# CH32V467VET-R0.net
KiCad netlist of a schematic drawn in Altium Designer
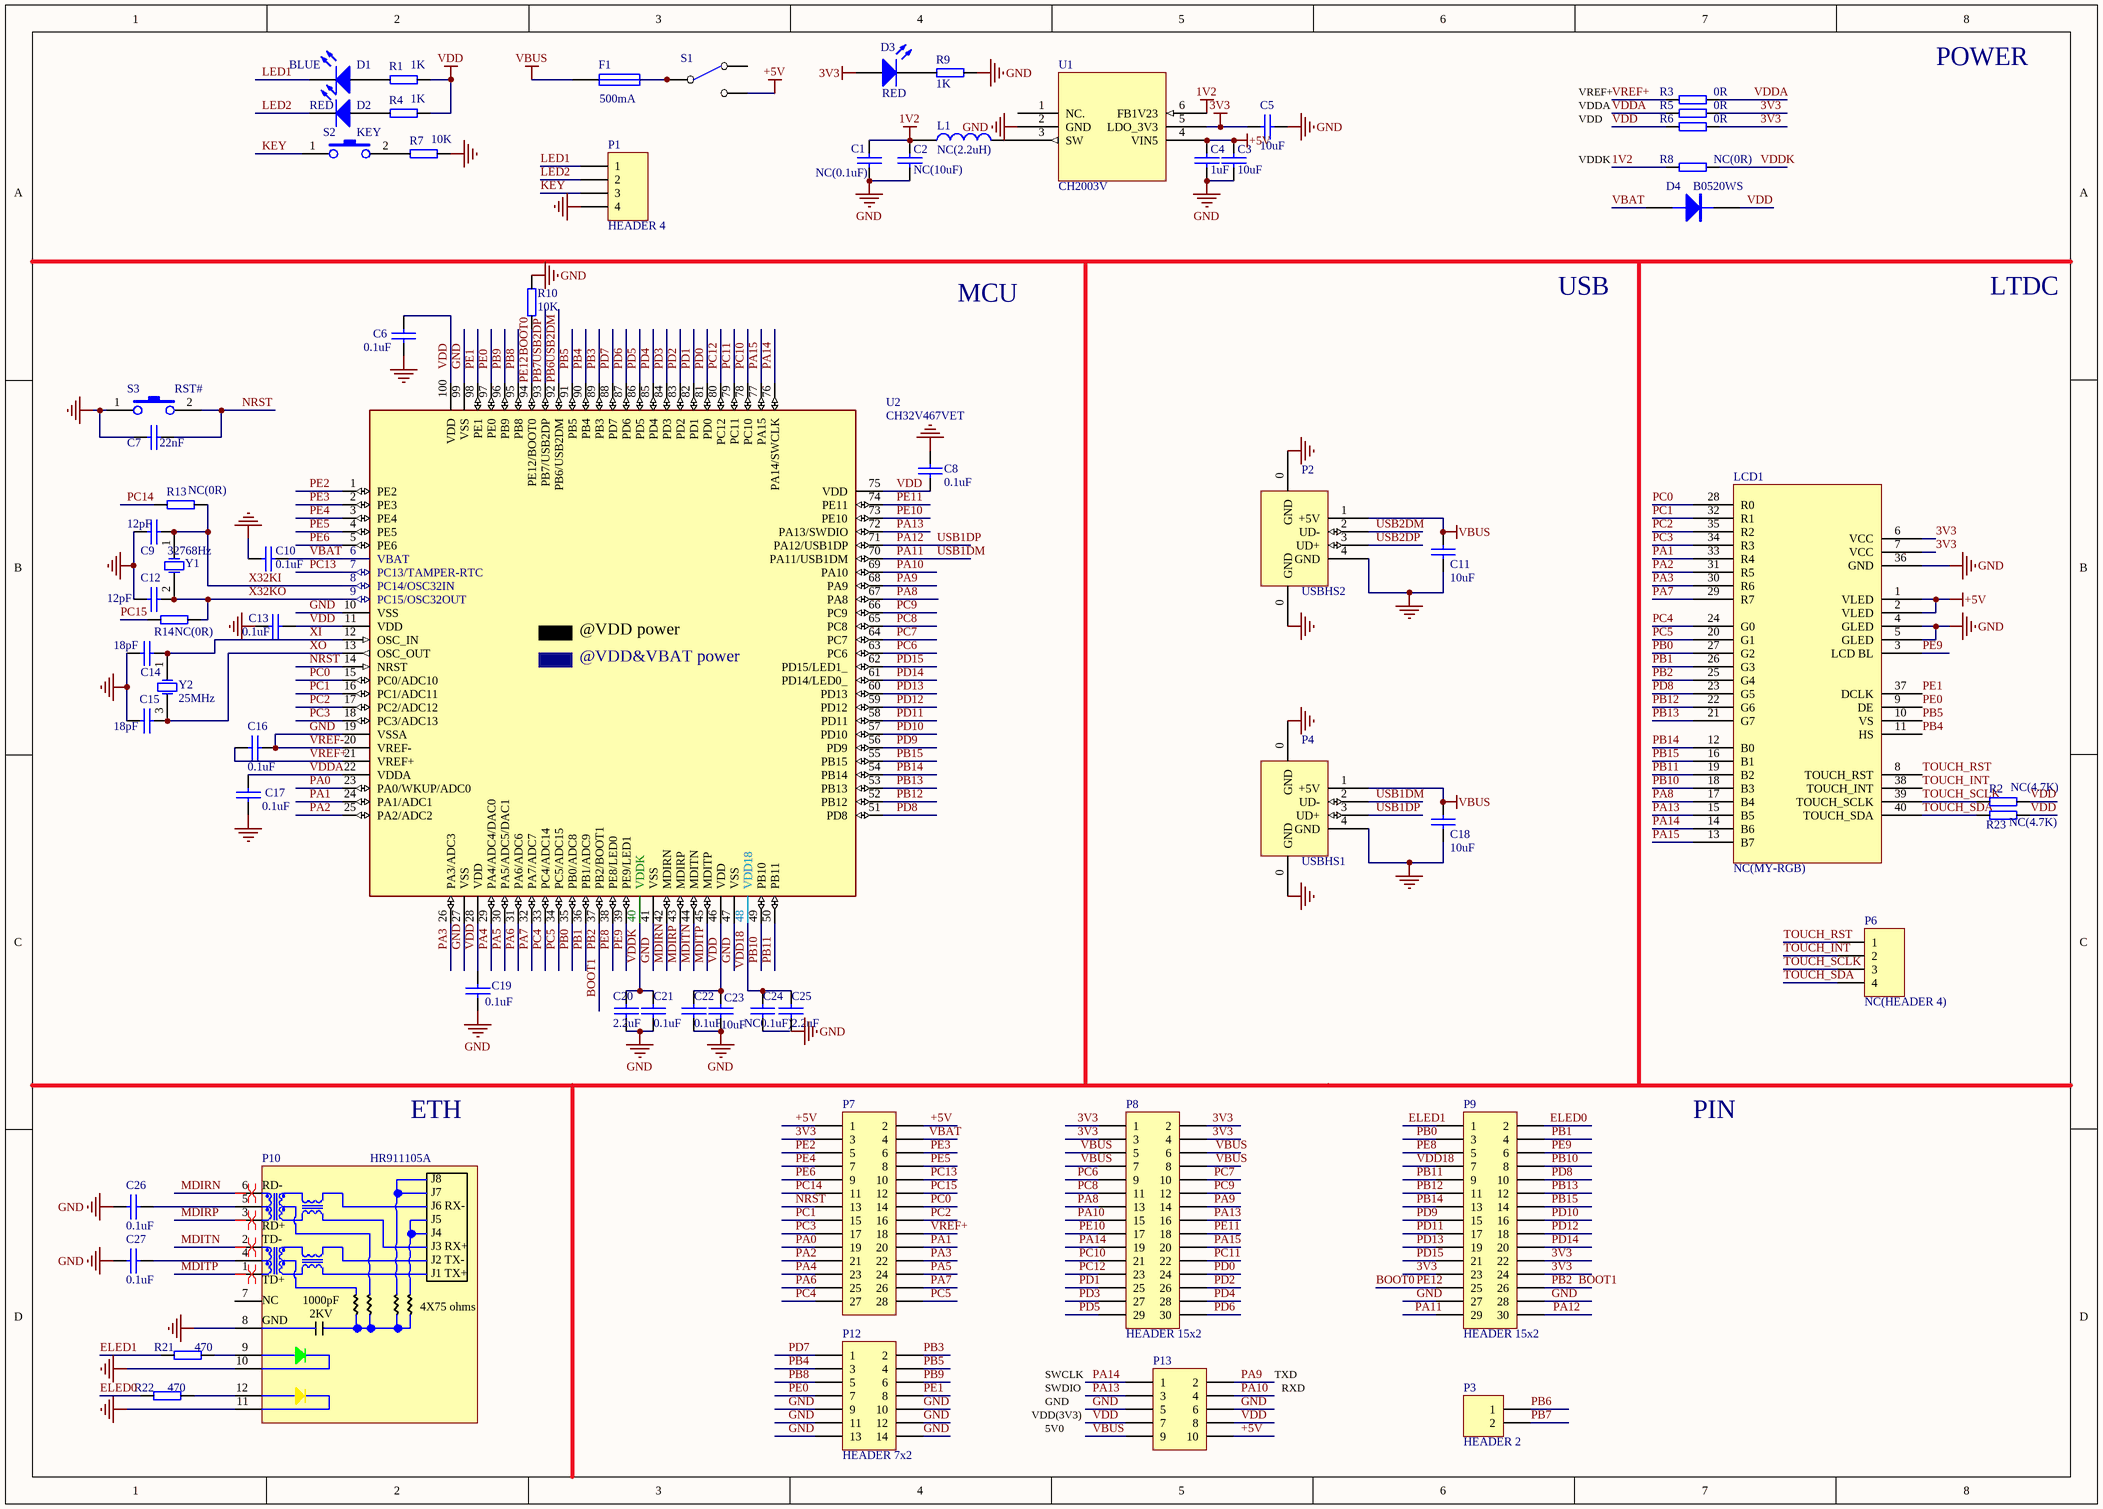
[diagram p0: CH32V467VET-R0.SchDoc]

(export (version "E")
  (design (tool "Eeschema 10.0.6"))
  (components
    (comp (ref "C1")
      (value "NC(0.1uF)")
      (footprint "0402_C")
      (description "Capacitor")
      (libsource (lib "") (part "CAP_2"))
    )
    (comp (ref "C2")
      (value "NC(10uF)")
      (footprint "0603_C")
      (description "Capacitor")
      (libsource (lib "*") (part "CAP"))
    )
    (comp (ref "C3")
      (value "10uF")
      (footprint "0603_C")
      (description "Capacitor")
      (libsource (lib "*") (part "CAP"))
    )
    (comp (ref "C4")
      (value "1uF")
      (footprint "0402_C")
      (description "Capacitor")
      (libsource (lib "") (part "CAP_2"))
    )
    (comp (ref "C5")
      (value "10uF")
      (footprint "0603_C")
      (description "Capacitor")
      (libsource (lib "*") (part "CAP"))
    )
    (comp (ref "C6")
      (value "0.1uF")
      (footprint "0402_C")
      (description "Capacitor")
      (libsource (lib "*") (part "CAP"))
    )
    (comp (ref "C7")
      (value "22nF")
      (footprint "0402_C")
      (description "Capacitor")
      (libsource (lib "") (part "CAP_1"))
    )
    (comp (ref "C8")
      (value "0.1uF")
      (footprint "0402_C")
      (description "Capacitor")
      (libsource (lib "*") (part "CAP"))
    )
    (comp (ref "C9")
      (value "12pF")
      (footprint "0402_C")
      (description "Capacitor")
      (libsource (lib "*") (part "CAP"))
    )
    (comp (ref "C10")
      (value "0.1uF")
      (footprint "0402_C")
      (description "Capacitor")
      (libsource (lib "*") (part "CAP"))
    )
    (comp (ref "C11")
      (value "10uF")
      (footprint "0603_C")
      (description "Capacitor")
      (libsource (lib "") (part "CAP_1"))
    )
    (comp (ref "C12")
      (value "12pF")
      (footprint "0402_C")
      (description "Capacitor")
      (libsource (lib "*") (part "CAP"))
    )
    (comp (ref "C13")
      (value "0.1uF")
      (footprint "0402_C")
      (description "Capacitor")
      (libsource (lib "*") (part "CAP"))
    )
    (comp (ref "C14")
      (value "18pF")
      (footprint "0402_C")
      (description "Capacitor")
      (libsource (lib "*") (part "CAP"))
    )
    (comp (ref "C15")
      (value "18pF")
      (footprint "0402_C")
      (description "Capacitor")
      (libsource (lib "*") (part "CAP"))
    )
    (comp (ref "C16")
      (value "0.1uF")
      (footprint "0402_C")
      (description "Capacitor")
      (libsource (lib "*") (part "CAP"))
    )
    (comp (ref "C17")
      (value "0.1uF")
      (footprint "0402_C")
      (description "Capacitor")
      (libsource (lib "*") (part "CAP"))
    )
    (comp (ref "C18")
      (value "10uF")
      (footprint "0603_C")
      (description "Capacitor")
      (libsource (lib "") (part "CAP_1"))
    )
    (comp (ref "C19")
      (value "0.1uF")
      (footprint "0402_C")
      (description "Capacitor")
      (libsource (lib "*") (part "CAP"))
    )
    (comp (ref "C20")
      (value "2.2uF")
      (footprint "0402_C")
      (description "Capacitor")
      (libsource (lib "*") (part "CAP"))
    )
    (comp (ref "C21")
      (value "0.1uF")
      (footprint "0402_C")
      (description "Capacitor")
      (libsource (lib "*") (part "CAP"))
    )
    (comp (ref "C22")
      (value "0.1uF")
      (footprint "0402_C")
      (description "Capacitor")
      (libsource (lib "*") (part "CAP"))
    )
    (comp (ref "C23")
      (value "10uF")
      (footprint "0603_C")
      (description "Capacitor")
      (libsource (lib "wch_sch_others") (part "CAP"))
    )
    (comp (ref "C24")
      (value "NC0.1uF)")
      (footprint "0402_C")
      (description "Capacitor")
      (libsource (lib "*") (part "CAP"))
    )
    (comp (ref "C25")
      (value "2.2uF")
      (footprint "0402_C")
      (description "Capacitor")
      (libsource (lib "*") (part "CAP"))
    )
    (comp (ref "C26")
      (value "0.1uF")
      (footprint "0402_C")
      (description "Capacitor")
      (libsource (lib "wch_sch_others") (part "CAP"))
    )
    (comp (ref "C27")
      (value "0.1uF")
      (footprint "0402_C")
      (description "Capacitor")
      (libsource (lib "wch_sch_others") (part "CAP"))
    )
    (comp (ref "D1")
      (value "BLUE")
      (footprint "0603+")
      (description "Typical INFRARED GaAs LED")
      (fields (field (name "PUBLISHER") "Altium Limited"))
      (libsource (lib "*") (part "LED0"))
    )
    (comp (ref "D2")
      (value "RED")
      (footprint "0603+")
      (description "Typical INFRARED GaAs LED")
      (fields (field (name "PUBLISHER") "Altium Limited"))
      (libsource (lib "*") (part "LED0"))
    )
    (comp (ref "D3")
      (value "RED")
      (footprint "0603+")
      (description "Typical INFRARED GaAs LED")
      (fields (field (name "PUBLISHER") "Altium Limited"))
      (libsource (lib "*") (part "LED0"))
    )
    (comp (ref "D4")
      (value "B0520WS")
      (footprint "SOD-323")
      (description "Diode")
      (libsource (lib "*") (part "DIODE"))
    )
    (comp (ref "F1")
      (value "500mA")
      (footprint "0603")
      (description "Fuse")
      (libsource (lib "wch_sch_others") (part "FUSE1"))
    )
    (comp (ref "L1") (value "NC(2.2uH)") (footprint "CD32") (libsource (lib "*") (part "INDUCTOR")))
    (comp (ref "LCD1")
      (value "NC(MY-RGB)")
      (footprint "FPC40P-0.5-FK750M3")
      (libsource (lib "MY-显示") (part "MY-RGB"))
    )
    (comp (ref "P1")
      (value "HEADER 4")
      (footprint "SIP4-2.54mm")
      (description "Header, 4-Pin")
      (libsource (lib "wch_sch_others") (part "HEADER 4"))
    )
    (comp (ref "P2")
      (value "USBHS2")
      (footprint "USBAF")
      (description "USB Port")
      (libsource (lib "*") (part "USB"))
    )
    (comp (ref "P3")
      (value "HEADER 2")
      (footprint "MYPCB:SIP2-2.54mm")
      (description "Header, 2-Pin")
      (libsource (lib "wch_sch_others") (part "HEADER 2"))
    )
    (comp (ref "P4")
      (value "USBHS1")
      (footprint "USBAF")
      (description "USB Port")
      (libsource (lib "*") (part "USB"))
    )
    (comp (ref "P6")
      (value "NC(HEADER 4)")
      (footprint "SIP4-2.54mm")
      (description "Header, 4-Pin")
      (libsource (lib "wch_sch_others") (part "HEADER 4"))
    )
    (comp (ref "P7")
      (value "HEADER 14x2")
      (footprint "MYPCB:IDC28-2.54MM")
      (description "Header, 14-Pin, Dual row")
      (libsource (lib "wch_sch_others") (part "HEADER 14x2"))
    )
    (comp (ref "P8")
      (value "HEADER 15x2")
      (footprint "MYPCB:IDC30-2.54MM")
      (description "Header, 15-Pin, Dual row")
      (libsource (lib "wch_sch_others") (part "HEADER 15x2"))
    )
    (comp (ref "P9")
      (value "HEADER 15x2")
      (footprint "MYPCB:IDC30-2.54MM")
      (description "Header, 15-Pin, Dual row")
      (libsource (lib "wch_sch_others") (part "HEADER 15x2"))
    )
    (comp (ref "P10") (value "HR911105A") (footprint "HR911105A") (libsource (lib "*") (part "HR911105A")))
    (comp (ref "P12")
      (value "HEADER 7x2")
      (footprint "MYPCB:IDC14-2.54mm")
      (description "Header, 7-Pin, Dual row")
      (libsource (lib "wch_sch_others") (part "HEADER 7x2"))
    )
    (comp (ref "P13")
      (value "LINK")
      (footprint "IDC10-2.54mm")
      (description "Header, 5-Pin, Dual row, Right Angle")
      (fields (field (name "PUBLISHER") "Altium Limited"))
      (libsource (lib "Miscellaneous Connectors") (part "Header 5X2H"))
    )
    (comp (ref "R1") (value "1K") (footprint "0402") (libsource (lib "wch_sch_others") (part "RES")))
    (comp (ref "R2") (value "NC(4.7K)") (footprint "0402") (libsource (lib "wch_sch_others") (part "RES")))
    (comp (ref "R3") (value "0R") (footprint "0402") (libsource (lib "*") (part "R")))
    (comp (ref "R4") (value "1K") (footprint "0402") (libsource (lib "wch_sch_others") (part "RES")))
    (comp (ref "R5") (value "0R") (footprint "0402") (libsource (lib "*") (part "R")))
    (comp (ref "R6") (value "0R") (footprint "0402") (libsource (lib "*") (part "R")))
    (comp (ref "R7") (value "10K") (footprint "0402") (libsource (lib "wch_sch_others") (part "RES")))
    (comp (ref "R8") (value "NC(0R)") (footprint "0402") (libsource (lib "*") (part "R")))
    (comp (ref "R9") (value "1K") (footprint "0402") (libsource (lib "wch_sch_others") (part "RES")))
    (comp (ref "R10") (value "10K") (footprint "0402") (libsource (lib "wch_sch_others") (part "RES")))
    (comp (ref "R13") (value "NC(0R)") (footprint "0402") (libsource (lib "wch_sch_others") (part "RES")))
    (comp (ref "R14") (value "NC(0R)") (footprint "0402") (libsource (lib "wch_sch_others") (part "RES")))
    (comp (ref "R21") (value "470") (footprint "0402") (libsource (lib "wch_sch_others") (part "RES")))
    (comp (ref "R22") (value "470") (footprint "0402") (libsource (lib "wch_sch_others") (part "RES")))
    (comp (ref "R23") (value "NC(4.7K)") (footprint "0402") (libsource (lib "wch_sch_others") (part "RES")))
    (comp (ref "S1") (value "SW SPDT") (footprint "SW1") (libsource (lib "*") (part "SW SPDT")))
    (comp (ref "S2")
      (value "KEY")
      (footprint "SMD_6.1x3.65x2.5mm-KEY")
      (libsource (lib "wch_sch_others") (part "KEY1"))
    )
    (comp (ref "S3")
      (value "RST#")
      (footprint "SMD_6.1x3.65x2.5mm-KEY")
      (libsource (lib "wch_sch_others") (part "KEY1"))
    )
    (comp (ref "U1")
      (value "CH2003V")
      (footprint "SOT-23-6")
      (description "Step-Down DC-DC Converter, 5V input, 1.23V * 800mA output, with LDO 3.3V * 200mA")
      (libsource (lib "CHXXX") (part "CH2003V"))
    )
    (comp (ref "U2")
      (value "CH32V467VET")
      (footprint "LQFP100")
      (description "RISC-V FPU HD-MCU, 175MHz, USB_480M, 100M Ethernet & Phy, CAN, DVP, ADC, DAC, SRAM")
      (libsource (lib "CHXXX") (part "CH32V467VET"))
    )
    (comp (ref "Y1")
      (value "32768Hz")
      (footprint "FC-135")
      (description "Crystal Oscillator")
      (fields (field (name "PUBLISHER") "Altium Limited"))
      (libsource (lib "") (part "XTAL_1"))
    )
    (comp (ref "Y2")
      (value "25MHz")
      (footprint "XT3225")
      (description "Crystal Oscillator")
      (fields (field (name "PUBLISHER") "Altium Limited"))
      (libsource (lib "*") (part "XTAL"))
    )
  )
  (nets
    (net (code "1") (name "+5V") (class "Default")
      (node (ref "C3") (pin "2") (pinfunction "2_2") (pintype "passive"))
      (node (ref "C4") (pin "2") (pinfunction "2_2") (pintype "passive"))
      (node (ref "LCD1") (pin "1") (pinfunction "VLED_1") (pintype "passive"))
      (node (ref "LCD1") (pin "2") (pinfunction "VLED_2") (pintype "passive"))
      (node (ref "P13") (pin "10") (pinfunction "10_10") (pintype "passive"))
      (node (ref "P7") (pin "1") (pinfunction "1_1") (pintype "passive"))
      (node (ref "P7") (pin "2") (pinfunction "2_2") (pintype "passive"))
      (node (ref "S1") (pin "2") (pinfunction "NC_2") (pintype "passive"))
      (node (ref "U1") (pin "4") (pinfunction "VIN5_4") (pintype "power_in"))
    )
    (net (code "3") (name "/BOOT0") (class "Default")
      (node (ref "P9") (pin "25") (pinfunction "25_25") (pintype "passive"))
      (node (ref "R10") (pin "2") (pintype "passive"))
      (node (ref "U2") (pin "94") (pinfunction "PE12/BOOT0_94") (pintype "bidirectional"))
    )
    (net (code "4") (name "/BOOT1") (class "Default")
      (node (ref "LCD1") (pin "25") (pinfunction "G4_25") (pintype "passive"))
      (node (ref "P9") (pin "26") (pinfunction "26_26") (pintype "passive"))
      (node (ref "U2") (pin "37") (pinfunction "PB2/BOOT1_37") (pintype "bidirectional"))
    )
    (net (code "5") (name "/ELED0") (class "Default")
      (node (ref "P9") (pin "2") (pinfunction "2_2") (pintype "passive"))
      (node (ref "R22") (pin "1") (pintype "passive"))
    )
    (net (code "6") (name "/ELED1") (class "Default")
      (node (ref "P9") (pin "1") (pinfunction "1_1") (pintype "passive"))
      (node (ref "R21") (pin "1") (pintype "passive"))
    )
    (net (code "7") (name "/KEY") (class "Default")
      (node (ref "P1") (pin "3") (pinfunction "3_3") (pintype "passive"))
      (node (ref "S2") (pin "1") (pinfunction "1_1") (pintype "passive"))
    )
    (net (code "8") (name "/LED1") (class "Default")
      (node (ref "D1") (pin "2") (pinfunction "K_2") (pintype "passive"))
      (node (ref "P1") (pin "1") (pinfunction "1_1") (pintype "passive"))
    )
    (net (code "9") (name "/LED2") (class "Default")
      (node (ref "D2") (pin "2") (pinfunction "K_2") (pintype "passive"))
      (node (ref "P1") (pin "2") (pinfunction "2_2") (pintype "passive"))
    )
    (net (code "10") (name "/MDIRN") (class "Default")
      (node (ref "P10") (pin "6") (pintype "passive"))
      (node (ref "U2") (pin "42") (pinfunction "MDIRN_42") (pintype "bidirectional"))
    )
    (net (code "11") (name "/MDIRP") (class "Default")
      (node (ref "P10") (pin "3") (pintype "passive"))
      (node (ref "U2") (pin "43") (pinfunction "MDIRP_43") (pintype "bidirectional"))
    )
    (net (code "12") (name "/MDITN") (class "Default")
      (node (ref "P10") (pin "2") (pintype "passive"))
      (node (ref "U2") (pin "44") (pinfunction "MDITN_44") (pintype "bidirectional"))
    )
    (net (code "13") (name "/MDITP") (class "Default")
      (node (ref "P10") (pin "1") (pintype "passive"))
      (node (ref "U2") (pin "45") (pinfunction "MDITP_45") (pintype "bidirectional"))
    )
    (net (code "14") (name "/NRST") (class "Default")
      (node (ref "C7") (pin "2") (pinfunction "2_2") (pintype "passive"))
      (node (ref "P7") (pin "13") (pinfunction "13_13") (pintype "passive"))
      (node (ref "S3") (pin "2") (pinfunction "2_2") (pintype "passive"))
      (node (ref "U2") (pin "14") (pinfunction "NRST_14") (pintype "input"))
    )
    (net (code "15") (name "/PA0") (class "Default")
      (node (ref "P7") (pin "19") (pinfunction "19_19") (pintype "passive"))
      (node (ref "U2") (pin "23") (pinfunction "PA0/WKUP/ADC0_23") (pintype "bidirectional"))
    )
    (net (code "16") (name "/PA1") (class "Default")
      (node (ref "LCD1") (pin "33") (pinfunction "R4_33") (pintype "passive"))
      (node (ref "P7") (pin "20") (pinfunction "20_20") (pintype "passive"))
      (node (ref "U2") (pin "24") (pinfunction "PA1/ADC1_24") (pintype "bidirectional"))
    )
    (net (code "17") (name "/PA2") (class "Default")
      (node (ref "LCD1") (pin "31") (pinfunction "R5_31") (pintype "passive"))
      (node (ref "P7") (pin "21") (pinfunction "21_21") (pintype "passive"))
      (node (ref "U2") (pin "25") (pinfunction "PA2/ADC2_25") (pintype "bidirectional"))
    )
    (net (code "18") (name "/PA3") (class "Default")
      (node (ref "LCD1") (pin "30") (pinfunction "R6_30") (pintype "passive"))
      (node (ref "P7") (pin "22") (pinfunction "22_22") (pintype "passive"))
      (node (ref "U2") (pin "26") (pinfunction "PA3/ADC3_26") (pintype "bidirectional"))
    )
    (net (code "19") (name "/PA4") (class "Default")
      (node (ref "P7") (pin "23") (pinfunction "23_23") (pintype "passive"))
      (node (ref "U2") (pin "29") (pinfunction "PA4/ADC4/DAC0_29") (pintype "bidirectional"))
    )
    (net (code "20") (name "/PA5") (class "Default")
      (node (ref "P7") (pin "24") (pinfunction "24_24") (pintype "passive"))
      (node (ref "U2") (pin "30") (pinfunction "PA5/ADC5/DAC1_30") (pintype "bidirectional"))
    )
    (net (code "21") (name "/PA6") (class "Default")
      (node (ref "P7") (pin "25") (pinfunction "25_25") (pintype "passive"))
      (node (ref "U2") (pin "31") (pinfunction "PA6/ADC6_31") (pintype "bidirectional"))
    )
    (net (code "22") (name "/PA7") (class "Default")
      (node (ref "LCD1") (pin "29") (pinfunction "R7_29") (pintype "passive"))
      (node (ref "P7") (pin "26") (pinfunction "26_26") (pintype "passive"))
      (node (ref "U2") (pin "32") (pinfunction "PA7/ADC7_32") (pintype "bidirectional"))
    )
    (net (code "23") (name "/PA8") (class "Default")
      (node (ref "LCD1") (pin "17") (pinfunction "B4_17") (pintype "passive"))
      (node (ref "P8") (pin "13") (pinfunction "13_13") (pintype "passive"))
      (node (ref "U2") (pin "67") (pinfunction "PA8_67") (pintype "bidirectional"))
    )
    (net (code "24") (name "/PA9") (class "Default")
      (node (ref "P13") (pin "2") (pinfunction "2_2") (pintype "passive"))
      (node (ref "P8") (pin "14") (pinfunction "14_14") (pintype "passive"))
      (node (ref "U2") (pin "68") (pinfunction "PA9_68") (pintype "bidirectional"))
    )
    (net (code "25") (name "/PA10") (class "Default")
      (node (ref "P13") (pin "4") (pinfunction "4_4") (pintype "passive"))
      (node (ref "P8") (pin "15") (pinfunction "15_15") (pintype "passive"))
      (node (ref "U2") (pin "69") (pinfunction "PA10_69") (pintype "bidirectional"))
    )
    (net (code "26") (name "/PA11") (class "Default")
      (node (ref "P4") (pin "2") (pinfunction "UD-_2") (pintype "bidirectional"))
      (node (ref "P9") (pin "29") (pinfunction "29_29") (pintype "passive"))
      (node (ref "U2") (pin "70") (pinfunction "PA11/USB1DM_70") (pintype "bidirectional"))
    )
    (net (code "27") (name "/PA12") (class "Default")
      (node (ref "P4") (pin "3") (pinfunction "UD+_3") (pintype "bidirectional"))
      (node (ref "P9") (pin "30") (pinfunction "30_30") (pintype "passive"))
      (node (ref "U2") (pin "71") (pinfunction "PA12/USB1DP_71") (pintype "bidirectional"))
    )
    (net (code "28") (name "/PA13") (class "Default")
      (node (ref "LCD1") (pin "15") (pinfunction "B5_15") (pintype "passive"))
      (node (ref "P13") (pin "3") (pinfunction "3_3") (pintype "passive"))
      (node (ref "P8") (pin "16") (pinfunction "16_16") (pintype "passive"))
      (node (ref "U2") (pin "72") (pinfunction "PA13/SWDIO_72") (pintype "bidirectional"))
    )
    (net (code "29") (name "/PA14") (class "Default")
      (node (ref "LCD1") (pin "14") (pinfunction "B6_14") (pintype "passive"))
      (node (ref "P13") (pin "1") (pinfunction "1_1") (pintype "passive"))
      (node (ref "P8") (pin "19") (pinfunction "19_19") (pintype "passive"))
      (node (ref "U2") (pin "76") (pinfunction "PA14/SWCLK_76") (pintype "bidirectional"))
    )
    (net (code "30") (name "/PA15") (class "Default")
      (node (ref "LCD1") (pin "13") (pinfunction "B7_13") (pintype "passive"))
      (node (ref "P8") (pin "20") (pinfunction "20_20") (pintype "passive"))
      (node (ref "U2") (pin "77") (pinfunction "PA15_77") (pintype "bidirectional"))
    )
    (net (code "31") (name "/PB0") (class "Default")
      (node (ref "LCD1") (pin "27") (pinfunction "G2_27") (pintype "passive"))
      (node (ref "P9") (pin "3") (pinfunction "3_3") (pintype "passive"))
      (node (ref "U2") (pin "35") (pinfunction "PB0/ADC8_35") (pintype "bidirectional"))
    )
    (net (code "32") (name "/PB1") (class "Default")
      (node (ref "LCD1") (pin "26") (pinfunction "G3_26") (pintype "passive"))
      (node (ref "P9") (pin "4") (pinfunction "4_4") (pintype "passive"))
      (node (ref "U2") (pin "36") (pinfunction "PB1/ADC9_36") (pintype "bidirectional"))
    )
    (net (code "33") (name "/PB3") (class "Default")
      (node (ref "P12") (pin "2") (pinfunction "2_2") (pintype "passive"))
      (node (ref "U2") (pin "89") (pinfunction "PB3_89") (pintype "bidirectional"))
    )
    (net (code "34") (name "/PB4") (class "Default")
      (node (ref "LCD1") (pin "11") (pinfunction "HS_11") (pintype "passive"))
      (node (ref "P12") (pin "3") (pinfunction "3_3") (pintype "passive"))
      (node (ref "U2") (pin "90") (pinfunction "PB4_90") (pintype "bidirectional"))
    )
    (net (code "35") (name "/PB5") (class "Default")
      (node (ref "LCD1") (pin "10") (pinfunction "VS_10") (pintype "passive"))
      (node (ref "P12") (pin "4") (pinfunction "4_4") (pintype "passive"))
      (node (ref "U2") (pin "91") (pinfunction "PB5_91") (pintype "bidirectional"))
    )
    (net (code "36") (name "/PB6") (class "Default")
      (node (ref "P2") (pin "2") (pinfunction "UD-_2") (pintype "bidirectional"))
      (node (ref "P3") (pin "1") (pinfunction "1_1") (pintype "passive"))
      (node (ref "U2") (pin "92") (pinfunction "PB6/USB2DM_92") (pintype "bidirectional"))
    )
    (net (code "37") (name "/PB7") (class "Default")
      (node (ref "P2") (pin "3") (pinfunction "UD+_3") (pintype "bidirectional"))
      (node (ref "P3") (pin "2") (pinfunction "2_2") (pintype "passive"))
      (node (ref "U2") (pin "93") (pinfunction "PB7/USB2DP_93") (pintype "bidirectional"))
    )
    (net (code "38") (name "/PB8") (class "Default")
      (node (ref "P12") (pin "5") (pinfunction "5_5") (pintype "passive"))
      (node (ref "U2") (pin "95") (pinfunction "PB8_95") (pintype "bidirectional"))
    )
    (net (code "39") (name "/PB9") (class "Default")
      (node (ref "P12") (pin "6") (pinfunction "6_6") (pintype "passive"))
      (node (ref "U2") (pin "96") (pinfunction "PB9_96") (pintype "bidirectional"))
    )
    (net (code "40") (name "/PB10") (class "Default")
      (node (ref "LCD1") (pin "18") (pinfunction "B3_18") (pintype "passive"))
      (node (ref "P9") (pin "8") (pinfunction "8_8") (pintype "passive"))
      (node (ref "U2") (pin "49") (pinfunction "PB10_49") (pintype "bidirectional"))
    )
    (net (code "41") (name "/PB11") (class "Default")
      (node (ref "LCD1") (pin "19") (pinfunction "B2_19") (pintype "passive"))
      (node (ref "P9") (pin "9") (pinfunction "9_9") (pintype "passive"))
      (node (ref "U2") (pin "50") (pinfunction "PB11_50") (pintype "bidirectional"))
    )
    (net (code "42") (name "/PB12") (class "Default")
      (node (ref "LCD1") (pin "22") (pinfunction "G6_22") (pintype "passive"))
      (node (ref "P9") (pin "11") (pinfunction "11_11") (pintype "passive"))
      (node (ref "U2") (pin "52") (pinfunction "PB12_52") (pintype "bidirectional"))
    )
    (net (code "43") (name "/PB13") (class "Default")
      (node (ref "LCD1") (pin "21") (pinfunction "G7_21") (pintype "passive"))
      (node (ref "P9") (pin "12") (pinfunction "12_12") (pintype "passive"))
      (node (ref "U2") (pin "53") (pinfunction "PB13_53") (pintype "bidirectional"))
    )
    (net (code "44") (name "/PB14") (class "Default")
      (node (ref "LCD1") (pin "12") (pinfunction "B0_12") (pintype "passive"))
      (node (ref "P9") (pin "13") (pinfunction "13_13") (pintype "passive"))
      (node (ref "U2") (pin "54") (pinfunction "PB14_54") (pintype "bidirectional"))
    )
    (net (code "45") (name "/PB15") (class "Default")
      (node (ref "LCD1") (pin "16") (pinfunction "B1_16") (pintype "passive"))
      (node (ref "P9") (pin "14") (pinfunction "14_14") (pintype "passive"))
      (node (ref "U2") (pin "55") (pinfunction "PB15_55") (pintype "bidirectional"))
    )
    (net (code "46") (name "/PC0") (class "Default")
      (node (ref "LCD1") (pin "28") (pinfunction "R0_28") (pintype "passive"))
      (node (ref "P7") (pin "14") (pinfunction "14_14") (pintype "passive"))
      (node (ref "U2") (pin "15") (pinfunction "PC0/ADC10_15") (pintype "bidirectional"))
    )
    (net (code "47") (name "/PC1") (class "Default")
      (node (ref "LCD1") (pin "32") (pinfunction "R1_32") (pintype "passive"))
      (node (ref "P7") (pin "15") (pinfunction "15_15") (pintype "passive"))
      (node (ref "U2") (pin "16") (pinfunction "PC1/ADC11_16") (pintype "bidirectional"))
    )
    (net (code "48") (name "/PC2") (class "Default")
      (node (ref "LCD1") (pin "35") (pinfunction "R2_35") (pintype "passive"))
      (node (ref "P7") (pin "16") (pinfunction "16_16") (pintype "passive"))
      (node (ref "U2") (pin "17") (pinfunction "PC2/ADC12_17") (pintype "bidirectional"))
    )
    (net (code "49") (name "/PC3") (class "Default")
      (node (ref "LCD1") (pin "34") (pinfunction "R3_34") (pintype "passive"))
      (node (ref "P7") (pin "17") (pinfunction "17_17") (pintype "passive"))
      (node (ref "U2") (pin "18") (pinfunction "PC3/ADC13_18") (pintype "bidirectional"))
    )
    (net (code "50") (name "/PC4") (class "Default")
      (node (ref "LCD1") (pin "24") (pinfunction "G0_24") (pintype "passive"))
      (node (ref "P7") (pin "27") (pinfunction "27_27") (pintype "passive"))
      (node (ref "U2") (pin "33") (pinfunction "PC4/ADC14_33") (pintype "bidirectional"))
    )
    (net (code "51") (name "/PC5") (class "Default")
      (node (ref "LCD1") (pin "20") (pinfunction "G1_20") (pintype "passive"))
      (node (ref "P7") (pin "28") (pinfunction "28_28") (pintype "passive"))
      (node (ref "U2") (pin "34") (pinfunction "PC5/ADC15_34") (pintype "bidirectional"))
    )
    (net (code "52") (name "/PC6") (class "Default")
      (node (ref "P8") (pin "9") (pinfunction "9_9") (pintype "passive"))
      (node (ref "U2") (pin "63") (pinfunction "PC6_63") (pintype "bidirectional"))
    )
    (net (code "53") (name "/PC7") (class "Default")
      (node (ref "P8") (pin "10") (pinfunction "10_10") (pintype "passive"))
      (node (ref "U2") (pin "64") (pinfunction "PC7_64") (pintype "bidirectional"))
    )
    (net (code "54") (name "/PC8") (class "Default")
      (node (ref "P8") (pin "11") (pinfunction "11_11") (pintype "passive"))
      (node (ref "U2") (pin "65") (pinfunction "PC8_65") (pintype "bidirectional"))
    )
    (net (code "55") (name "/PC9") (class "Default")
      (node (ref "P8") (pin "12") (pinfunction "12_12") (pintype "passive"))
      (node (ref "U2") (pin "66") (pinfunction "PC9_66") (pintype "bidirectional"))
    )
    (net (code "56") (name "/PC10") (class "Default")
      (node (ref "P8") (pin "21") (pinfunction "21_21") (pintype "passive"))
      (node (ref "U2") (pin "78") (pinfunction "PC10_78") (pintype "bidirectional"))
    )
    (net (code "57") (name "/PC11") (class "Default")
      (node (ref "P8") (pin "22") (pinfunction "22_22") (pintype "passive"))
      (node (ref "U2") (pin "79") (pinfunction "PC11_79") (pintype "bidirectional"))
    )
    (net (code "58") (name "/PC12") (class "Default")
      (node (ref "P8") (pin "23") (pinfunction "23_23") (pintype "passive"))
      (node (ref "U2") (pin "80") (pinfunction "PC12_80") (pintype "bidirectional"))
    )
    (net (code "59") (name "/PC13") (class "Default")
      (node (ref "P7") (pin "10") (pinfunction "10_10") (pintype "passive"))
      (node (ref "U2") (pin "7") (pinfunction "PC13/TAMPER-RTC_7") (pintype "bidirectional"))
    )
    (net (code "60") (name "/PC14") (class "Default")
      (node (ref "P7") (pin "11") (pinfunction "11_11") (pintype "passive"))
      (node (ref "R13") (pin "1") (pintype "passive"))
    )
    (net (code "61") (name "/PC15") (class "Default")
      (node (ref "P7") (pin "12") (pinfunction "12_12") (pintype "passive"))
      (node (ref "R14") (pin "1") (pintype "passive"))
    )
    (net (code "62") (name "/PD0") (class "Default")
      (node (ref "P8") (pin "24") (pinfunction "24_24") (pintype "passive"))
      (node (ref "U2") (pin "81") (pinfunction "PD0_81") (pintype "bidirectional"))
    )
    (net (code "63") (name "/PD1") (class "Default")
      (node (ref "P8") (pin "25") (pinfunction "25_25") (pintype "passive"))
      (node (ref "U2") (pin "82") (pinfunction "PD1_82") (pintype "bidirectional"))
    )
    (net (code "64") (name "/PD2") (class "Default")
      (node (ref "P8") (pin "26") (pinfunction "26_26") (pintype "passive"))
      (node (ref "U2") (pin "83") (pinfunction "PD2_83") (pintype "bidirectional"))
    )
    (net (code "65") (name "/PD3") (class "Default")
      (node (ref "P8") (pin "27") (pinfunction "27_27") (pintype "passive"))
      (node (ref "U2") (pin "84") (pinfunction "PD3_84") (pintype "bidirectional"))
    )
    (net (code "66") (name "/PD4") (class "Default")
      (node (ref "P8") (pin "28") (pinfunction "28_28") (pintype "passive"))
      (node (ref "U2") (pin "85") (pinfunction "PD4_85") (pintype "bidirectional"))
    )
    (net (code "67") (name "/PD5") (class "Default")
      (node (ref "P8") (pin "29") (pinfunction "29_29") (pintype "passive"))
      (node (ref "U2") (pin "86") (pinfunction "PD5_86") (pintype "bidirectional"))
    )
    (net (code "68") (name "/PD6") (class "Default")
      (node (ref "P8") (pin "30") (pinfunction "30_30") (pintype "passive"))
      (node (ref "U2") (pin "87") (pinfunction "PD6_87") (pintype "bidirectional"))
    )
    (net (code "69") (name "/PD7") (class "Default")
      (node (ref "P12") (pin "1") (pinfunction "1_1") (pintype "passive"))
      (node (ref "U2") (pin "88") (pinfunction "PD7_88") (pintype "bidirectional"))
    )
    (net (code "70") (name "/PD8") (class "Default")
      (node (ref "LCD1") (pin "23") (pinfunction "G5_23") (pintype "passive"))
      (node (ref "P9") (pin "10") (pinfunction "10_10") (pintype "passive"))
      (node (ref "U2") (pin "51") (pinfunction "PD8_51") (pintype "bidirectional"))
    )
    (net (code "71") (name "/PD9") (class "Default")
      (node (ref "P9") (pin "15") (pinfunction "15_15") (pintype "passive"))
      (node (ref "U2") (pin "56") (pinfunction "PD9_56") (pintype "bidirectional"))
    )
    (net (code "72") (name "/PD10") (class "Default")
      (node (ref "P9") (pin "16") (pinfunction "16_16") (pintype "passive"))
      (node (ref "U2") (pin "57") (pinfunction "PD10_57") (pintype "bidirectional"))
    )
    (net (code "73") (name "/PD11") (class "Default")
      (node (ref "P9") (pin "17") (pinfunction "17_17") (pintype "passive"))
      (node (ref "U2") (pin "58") (pinfunction "PD11_58") (pintype "bidirectional"))
    )
    (net (code "74") (name "/PD12") (class "Default")
      (node (ref "P9") (pin "18") (pinfunction "18_18") (pintype "passive"))
      (node (ref "U2") (pin "59") (pinfunction "PD12_59") (pintype "bidirectional"))
    )
    (net (code "75") (name "/PD13") (class "Default")
      (node (ref "P9") (pin "19") (pinfunction "19_19") (pintype "passive"))
      (node (ref "U2") (pin "60") (pinfunction "PD13_60") (pintype "bidirectional"))
    )
    (net (code "76") (name "/PD14") (class "Default")
      (node (ref "P9") (pin "20") (pinfunction "20_20") (pintype "passive"))
      (node (ref "U2") (pin "61") (pinfunction "PD14/LED0__61") (pintype "bidirectional"))
    )
    (net (code "77") (name "/PD15") (class "Default")
      (node (ref "P9") (pin "21") (pinfunction "21_21") (pintype "passive"))
      (node (ref "U2") (pin "62") (pinfunction "PD15/LED1__62") (pintype "bidirectional"))
    )
    (net (code "78") (name "/PE0") (class "Default")
      (node (ref "LCD1") (pin "9") (pinfunction "DE_9") (pintype "passive"))
      (node (ref "P12") (pin "7") (pinfunction "7_7") (pintype "passive"))
      (node (ref "U2") (pin "97") (pinfunction "PE0_97") (pintype "bidirectional"))
    )
    (net (code "79") (name "/PE1") (class "Default")
      (node (ref "LCD1") (pin "37") (pinfunction "DCLK_37") (pintype "passive"))
      (node (ref "P12") (pin "8") (pinfunction "8_8") (pintype "passive"))
      (node (ref "U2") (pin "98") (pinfunction "PE1_98") (pintype "bidirectional"))
    )
    (net (code "80") (name "/PE2") (class "Default")
      (node (ref "P7") (pin "5") (pinfunction "5_5") (pintype "passive"))
      (node (ref "U2") (pin "1") (pinfunction "PE2_1") (pintype "bidirectional"))
    )
    (net (code "81") (name "/PE3") (class "Default")
      (node (ref "P7") (pin "6") (pinfunction "6_6") (pintype "passive"))
      (node (ref "U2") (pin "2") (pinfunction "PE3_2") (pintype "bidirectional"))
    )
    (net (code "82") (name "/PE4") (class "Default")
      (node (ref "P7") (pin "7") (pinfunction "7_7") (pintype "passive"))
      (node (ref "U2") (pin "3") (pinfunction "PE4_3") (pintype "bidirectional"))
    )
    (net (code "83") (name "/PE5") (class "Default")
      (node (ref "P7") (pin "8") (pinfunction "8_8") (pintype "passive"))
      (node (ref "U2") (pin "4") (pinfunction "PE5_4") (pintype "bidirectional"))
    )
    (net (code "84") (name "/PE6") (class "Default")
      (node (ref "P7") (pin "9") (pinfunction "9_9") (pintype "passive"))
      (node (ref "U2") (pin "5") (pinfunction "PE6_5") (pintype "bidirectional"))
    )
    (net (code "85") (name "/PE8") (class "Default")
      (node (ref "P9") (pin "5") (pinfunction "5_5") (pintype "passive"))
      (node (ref "U2") (pin "38") (pinfunction "PE8/LED0_38") (pintype "bidirectional"))
    )
    (net (code "86") (name "/PE9") (class "Default")
      (node (ref "LCD1") (pin "3") (pinfunction "LCD_BL_3") (pintype "passive"))
      (node (ref "P9") (pin "6") (pinfunction "6_6") (pintype "passive"))
      (node (ref "U2") (pin "39") (pinfunction "PE9/LED1_39") (pintype "bidirectional"))
    )
    (net (code "87") (name "/PE10") (class "Default")
      (node (ref "P8") (pin "17") (pinfunction "17_17") (pintype "passive"))
      (node (ref "U2") (pin "73") (pinfunction "PE10_73") (pintype "bidirectional"))
    )
    (net (code "88") (name "/PE11") (class "Default")
      (node (ref "P8") (pin "18") (pinfunction "18_18") (pintype "passive"))
      (node (ref "U2") (pin "74") (pinfunction "PE11_74") (pintype "bidirectional"))
    )
    (net (code "89") (name "/TOUCH_INT") (class "Default")
      (node (ref "LCD1") (pin "38") (pinfunction "TOUCH_INT_38") (pintype "passive"))
      (node (ref "P6") (pin "2") (pinfunction "2_2") (pintype "passive"))
    )
    (net (code "90") (name "/TOUCH_RST") (class "Default")
      (node (ref "LCD1") (pin "8") (pinfunction "TOUCH_RST_8") (pintype "passive"))
      (node (ref "P6") (pin "1") (pinfunction "1_1") (pintype "passive"))
    )
    (net (code "91") (name "/TOUCH_SCLK") (class "Default")
      (node (ref "LCD1") (pin "39") (pinfunction "TOUCH_SCLK_39") (pintype "passive"))
      (node (ref "P6") (pin "3") (pinfunction "3_3") (pintype "passive"))
      (node (ref "R2") (pin "2") (pintype "passive"))
    )
    (net (code "92") (name "/TOUCH_SDA") (class "Default")
      (node (ref "LCD1") (pin "40") (pinfunction "TOUCH_SDA_40") (pintype "passive"))
      (node (ref "P6") (pin "4") (pinfunction "4_4") (pintype "passive"))
      (node (ref "R23") (pin "2") (pintype "passive"))
    )
    (net (code "93") (name "/VBAT") (class "Default")
      (node (ref "C10") (pin "2") (pinfunction "2_2") (pintype "passive"))
      (node (ref "D4") (pin "1") (pinfunction "A_1") (pintype "passive"))
      (node (ref "P7") (pin "4") (pinfunction "4_4") (pintype "passive"))
      (node (ref "U2") (pin "6") (pinfunction "VBAT_6") (pintype "power_in"))
    )
    (net (code "94") (name "/VDD18") (class "Default")
      (node (ref "C24") (pin "2") (pinfunction "2_2") (pintype "passive"))
      (node (ref "C25") (pin "2") (pinfunction "2_2") (pintype "passive"))
      (node (ref "P9") (pin "7") (pinfunction "7_7") (pintype "passive"))
      (node (ref "U2") (pin "48") (pinfunction "VDD18_48") (pintype "power_in"))
    )
    (net (code "95") (name "/VDDA") (class "Default")
      (node (ref "C17") (pin "1") (pinfunction "1_1") (pintype "passive"))
      (node (ref "R3") (pin "1") (pinfunction "1_1") (pintype "passive"))
      (node (ref "R5") (pin "2") (pinfunction "2_2") (pintype "passive"))
      (node (ref "U2") (pin "22") (pinfunction "VDDA_22") (pintype "power_in"))
    )
    (net (code "96") (name "/VDDK") (class "Default")
      (node (ref "C20") (pin "2") (pinfunction "2_2") (pintype "passive"))
      (node (ref "C21") (pin "2") (pinfunction "2_2") (pintype "passive"))
      (node (ref "R8") (pin "1") (pinfunction "1_1") (pintype "passive"))
      (node (ref "U2") (pin "40") (pinfunction "VDDK_40") (pintype "power_in"))
    )
    (net (code "97") (name "/VREF+") (class "Default")
      (node (ref "C16") (pin "1") (pinfunction "1_1") (pintype "passive"))
      (node (ref "P7") (pin "18") (pinfunction "18_18") (pintype "passive"))
      (node (ref "R3") (pin "2") (pinfunction "2_2") (pintype "passive"))
      (node (ref "U2") (pin "21") (pinfunction "VREF+_21") (pintype "power_in"))
    )
    (net (code "98") (name "/X32KI") (class "Default")
      (node (ref "C9") (pin "2") (pinfunction "2_2") (pintype "passive"))
      (node (ref "R13") (pin "2") (pintype "passive"))
      (node (ref "U2") (pin "8") (pinfunction "PC14/OSC32IN_8") (pintype "bidirectional"))
      (node (ref "Y1") (pin "1") (pinfunction "OSC1_1") (pintype "passive"))
    )
    (net (code "99") (name "/X32KO") (class "Default")
      (node (ref "C12") (pin "2") (pinfunction "2_2") (pintype "passive"))
      (node (ref "R14") (pin "2") (pintype "passive"))
      (node (ref "U2") (pin "9") (pinfunction "PC15/OSC32OUT_9") (pintype "bidirectional"))
      (node (ref "Y1") (pin "2") (pinfunction "OSC2_2") (pintype "passive"))
    )
    (net (code "100") (name "/XI") (class "Default")
      (node (ref "C14") (pin "2") (pinfunction "2_2") (pintype "passive"))
      (node (ref "U2") (pin "12") (pinfunction "OSC_IN_12") (pintype "input"))
      (node (ref "Y2") (pin "1") (pinfunction "OSC1_1") (pintype "passive"))
    )
    (net (code "101") (name "/XO") (class "Default")
      (node (ref "C15") (pin "2") (pinfunction "2_2") (pintype "passive"))
      (node (ref "U2") (pin "13") (pinfunction "OSC_OUT_13") (pintype "output"))
      (node (ref "Y2") (pin "3") (pinfunction "OSC2_3") (pintype "passive"))
    )
    (net (code "102") (name "1V2") (class "Default")
      (node (ref "C1") (pin "2") (pinfunction "2_2") (pintype "passive"))
      (node (ref "C2") (pin "2") (pinfunction "2_2") (pintype "passive"))
      (node (ref "L1") (pin "2") (pinfunction "2_2") (pintype "passive"))
      (node (ref "R8") (pin "2") (pinfunction "2_2") (pintype "passive"))
      (node (ref "U1") (pin "6") (pinfunction "FB1V23_6") (pintype "input"))
    )
    (net (code "103") (name "3V3") (class "Default")
      (node (ref "C5") (pin "2") (pinfunction "2_2") (pintype "passive"))
      (node (ref "D3") (pin "1") (pinfunction "A_1") (pintype "passive"))
      (node (ref "LCD1") (pin "6") (pinfunction "VCC_6") (pintype "passive"))
      (node (ref "LCD1") (pin "7") (pinfunction "VCC_7") (pintype "passive"))
      (node (ref "P7") (pin "3") (pinfunction "3_3") (pintype "passive"))
      (node (ref "P8") (pin "1") (pinfunction "1_1") (pintype "passive"))
      (node (ref "P8") (pin "2") (pinfunction "2_2") (pintype "passive"))
      (node (ref "P8") (pin "3") (pinfunction "3_3") (pintype "passive"))
      (node (ref "P8") (pin "4") (pinfunction "4_4") (pintype "passive"))
      (node (ref "P9") (pin "22") (pinfunction "22_22") (pintype "passive"))
      (node (ref "P9") (pin "23") (pinfunction "23_23") (pintype "passive"))
      (node (ref "P9") (pin "24") (pinfunction "24_24") (pintype "passive"))
      (node (ref "R5") (pin "1") (pinfunction "1_1") (pintype "passive"))
      (node (ref "R6") (pin "1") (pinfunction "1_1") (pintype "passive"))
      (node (ref "U1") (pin "5") (pinfunction "LDO_3V3_5") (pintype "power_in"))
    )
    (net (code "104") (name "GND") (class "Default")
      (node (ref "C1") (pin "1") (pinfunction "1_1") (pintype "passive"))
      (node (ref "C10") (pin "1") (pinfunction "1_1") (pintype "passive"))
      (node (ref "C11") (pin "2") (pinfunction "2_2") (pintype "passive"))
      (node (ref "C12") (pin "1") (pinfunction "1_1") (pintype "passive"))
      (node (ref "C13") (pin "2") (pinfunction "2_2") (pintype "passive"))
      (node (ref "C14") (pin "1") (pinfunction "1_1") (pintype "passive"))
      (node (ref "C15") (pin "1") (pinfunction "1_1") (pintype "passive"))
      (node (ref "C16") (pin "2") (pinfunction "2_2") (pintype "passive"))
      (node (ref "C17") (pin "2") (pinfunction "2_2") (pintype "passive"))
      (node (ref "C18") (pin "2") (pinfunction "2_2") (pintype "passive"))
      (node (ref "C19") (pin "1") (pinfunction "1_1") (pintype "passive"))
      (node (ref "C2") (pin "1") (pinfunction "1_1") (pintype "passive"))
      (node (ref "C20") (pin "1") (pinfunction "1_1") (pintype "passive"))
      (node (ref "C21") (pin "1") (pinfunction "1_1") (pintype "passive"))
      (node (ref "C22") (pin "1") (pinfunction "1_1") (pintype "passive"))
      (node (ref "C23") (pin "1") (pinfunction "1_1") (pintype "passive"))
      (node (ref "C25") (pin "1") (pinfunction "1_1") (pintype "passive"))
      (node (ref "C26") (pin "1") (pinfunction "1_1") (pintype "passive"))
      (node (ref "C27") (pin "1") (pinfunction "1_1") (pintype "passive"))
      (node (ref "C3") (pin "1") (pinfunction "1_1") (pintype "passive"))
      (node (ref "C4") (pin "1") (pinfunction "1_1") (pintype "passive"))
      (node (ref "C5") (pin "1") (pinfunction "1_1") (pintype "passive"))
      (node (ref "C6") (pin "1") (pinfunction "1_1") (pintype "passive"))
      (node (ref "C7") (pin "1") (pinfunction "1_1") (pintype "passive"))
      (node (ref "C8") (pin "2") (pinfunction "2_2") (pintype "passive"))
      (node (ref "C9") (pin "1") (pinfunction "1_1") (pintype "passive"))
      (node (ref "LCD1") (pin "36") (pinfunction "GND_36") (pintype "passive"))
      (node (ref "LCD1") (pin "4") (pinfunction "GLED_4") (pintype "passive"))
      (node (ref "LCD1") (pin "5") (pinfunction "GLED_5") (pintype "passive"))
      (node (ref "P1") (pin "4") (pinfunction "4_4") (pintype "passive"))
      (node (ref "P10") (pin "10") (pintype "passive"))
      (node (ref "P10") (pin "11") (pintype "passive"))
      (node (ref "P10") (pin "8") (pintype "passive"))
      (node (ref "P12") (pin "10") (pinfunction "10_10") (pintype "passive"))
      (node (ref "P12") (pin "11") (pinfunction "11_11") (pintype "passive"))
      (node (ref "P12") (pin "12") (pinfunction "12_12") (pintype "passive"))
      (node (ref "P12") (pin "13") (pinfunction "13_13") (pintype "passive"))
      (node (ref "P12") (pin "14") (pinfunction "14_14") (pintype "passive"))
      (node (ref "P12") (pin "9") (pinfunction "9_9") (pintype "passive"))
      (node (ref "P13") (pin "5") (pinfunction "5_5") (pintype "passive"))
      (node (ref "P13") (pin "6") (pinfunction "6_6") (pintype "passive"))
      (node (ref "P2") (pin "0") (pinfunction "GND_0") (pintype "power_in"))
      (node (ref "P2") (pin "4") (pinfunction "GND_4") (pintype "power_in"))
      (node (ref "P4") (pin "0") (pinfunction "GND_0") (pintype "power_in"))
      (node (ref "P4") (pin "4") (pinfunction "GND_4") (pintype "power_in"))
      (node (ref "P9") (pin "27") (pinfunction "27_27") (pintype "passive"))
      (node (ref "P9") (pin "28") (pinfunction "28_28") (pintype "passive"))
      (node (ref "R10") (pin "1") (pintype "passive"))
      (node (ref "R7") (pin "1") (pintype "passive"))
      (node (ref "R9") (pin "2") (pintype "passive"))
      (node (ref "S3") (pin "1") (pinfunction "1_1") (pintype "passive"))
      (node (ref "U1") (pin "2") (pinfunction "GND_2") (pintype "power_in"))
      (node (ref "U2") (pin "10") (pinfunction "VSS_10") (pintype "power_in"))
      (node (ref "U2") (pin "19") (pinfunction "VSSA_19") (pintype "power_in"))
      (node (ref "U2") (pin "20") (pinfunction "VREF-_20") (pintype "power_in"))
      (node (ref "U2") (pin "27") (pinfunction "VSS_27") (pintype "power_in"))
      (node (ref "U2") (pin "41") (pinfunction "VSS_41") (pintype "power_in"))
      (node (ref "U2") (pin "47") (pinfunction "VSS_47") (pintype "power_in"))
      (node (ref "U2") (pin "99") (pinfunction "VSS_99") (pintype "power_in"))
    )
    (net (code "105") (name "Net-(C26-Pad2)") (class "Default")
      (node (ref "C26") (pin "2") (pinfunction "2_2") (pintype "passive"))
      (node (ref "P10") (pin "5") (pintype "passive"))
    )
    (net (code "106") (name "Net-(C27-Pad2)") (class "Default")
      (node (ref "C27") (pin "2") (pinfunction "2_2") (pintype "passive"))
      (node (ref "P10") (pin "4") (pintype "passive"))
    )
    (net (code "107") (name "Net-(D1-A)") (class "Default")
      (node (ref "D1") (pin "1") (pinfunction "A_1") (pintype "passive"))
      (node (ref "R1") (pin "2") (pintype "passive"))
    )
    (net (code "108") (name "Net-(D2-A)") (class "Default")
      (node (ref "D2") (pin "1") (pinfunction "A_1") (pintype "passive"))
      (node (ref "R4") (pin "2") (pintype "passive"))
    )
    (net (code "109") (name "Net-(D3-K)") (class "Default")
      (node (ref "D3") (pin "2") (pinfunction "K_2") (pintype "passive"))
      (node (ref "R9") (pin "1") (pintype "passive"))
    )
    (net (code "110") (name "Net-(P10-Pad9)") (class "Default")
      (node (ref "P10") (pin "9") (pintype "passive"))
      (node (ref "R21") (pin "2") (pintype "passive"))
    )
    (net (code "111") (name "Net-(P10-Pad12)") (class "Default")
      (node (ref "P10") (pin "12") (pintype "passive"))
      (node (ref "R22") (pin "2") (pintype "passive"))
    )
    (net (code "112") (name "Net-(R7-Pad2)") (class "Default")
      (node (ref "R7") (pin "2") (pintype "passive"))
      (node (ref "S2") (pin "2") (pinfunction "2_2") (pintype "passive"))
    )
    (net (code "113") (name "Net-(S1-COMMON)") (class "Default")
      (node (ref "F1") (pin "2") (pinfunction "2_2") (pintype "passive"))
      (node (ref "S1") (pin "1") (pinfunction "COMMON_1") (pintype "passive"))
    )
    (net (code "114") (name "Net-(U1-SW)") (class "Default")
      (node (ref "L1") (pin "1") (pinfunction "1_1") (pintype "passive"))
      (node (ref "U1") (pin "3") (pinfunction "SW_3") (pintype "output"))
    )
    (net (code "115") (name "VBUS") (class "Default")
      (node (ref "C11") (pin "1") (pinfunction "1_1") (pintype "passive"))
      (node (ref "C18") (pin "1") (pinfunction "1_1") (pintype "passive"))
      (node (ref "F1") (pin "1") (pinfunction "1_1") (pintype "passive"))
      (node (ref "P13") (pin "9") (pinfunction "9_9") (pintype "passive"))
      (node (ref "P2") (pin "1") (pinfunction "+5V_1") (pintype "power_in"))
      (node (ref "P4") (pin "1") (pinfunction "+5V_1") (pintype "power_in"))
      (node (ref "P8") (pin "5") (pinfunction "5_5") (pintype "passive"))
      (node (ref "P8") (pin "6") (pinfunction "6_6") (pintype "passive"))
      (node (ref "P8") (pin "7") (pinfunction "7_7") (pintype "passive"))
      (node (ref "P8") (pin "8") (pinfunction "8_8") (pintype "passive"))
    )
    (net (code "116") (name "VDD") (class "Default")
      (node (ref "C13") (pin "1") (pinfunction "1_1") (pintype "passive"))
      (node (ref "C19") (pin "2") (pinfunction "2_2") (pintype "passive"))
      (node (ref "C22") (pin "2") (pinfunction "2_2") (pintype "passive"))
      (node (ref "C23") (pin "2") (pinfunction "2_2") (pintype "passive"))
      (node (ref "C6") (pin "2") (pinfunction "2_2") (pintype "passive"))
      (node (ref "C8") (pin "1") (pinfunction "1_1") (pintype "passive"))
      (node (ref "D4") (pin "2") (pinfunction "K_2") (pintype "passive"))
      (node (ref "P13") (pin "7") (pinfunction "7_7") (pintype "passive"))
      (node (ref "P13") (pin "8") (pinfunction "8_8") (pintype "passive"))
      (node (ref "R1") (pin "1") (pintype "passive"))
      (node (ref "R2") (pin "1") (pintype "passive"))
      (node (ref "R23") (pin "1") (pintype "passive"))
      (node (ref "R4") (pin "1") (pintype "passive"))
      (node (ref "R6") (pin "2") (pinfunction "2_2") (pintype "passive"))
      (node (ref "U2") (pin "100") (pinfunction "VDD_100") (pintype "power_in"))
      (node (ref "U2") (pin "11") (pinfunction "VDD_11") (pintype "power_in"))
      (node (ref "U2") (pin "28") (pinfunction "VDD_28") (pintype "power_in"))
      (node (ref "U2") (pin "46") (pinfunction "VDD_46") (pintype "power_in"))
      (node (ref "U2") (pin "75") (pinfunction "VDD_75") (pintype "power_in"))
    )
    (net (code "117") (name "unconnected-(C24-Pad1)") (class "Default")
      (node (ref "C24") (pin "1") (pinfunction "1_1") (pintype "passive"))
    )
    (net (code "118") (name "unconnected-(P10-Pad7)") (class "Default")
      (node (ref "P10") (pin "7") (pintype "passive"))
    )
    (net (code "119") (name "unconnected-(S1-NO-Pad3)") (class "Default")
      (node (ref "S1") (pin "3") (pinfunction "NO_3") (pintype "passive"))
    )
    (net (code "120") (name "unconnected-(U1-NC.-Pad1)") (class "Default")
      (node (ref "U1") (pin "1") (pinfunction "NC._1") (pintype "passive"))
    )
  )
)
